# power_mux-v5.net
KiCad netlist of a schematic drawn in EAGLE
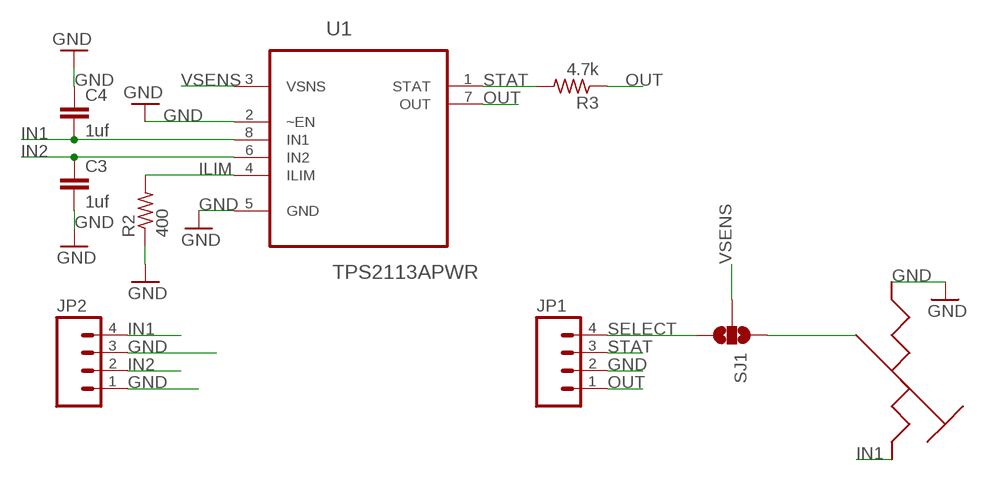
[diagram p0: schematic, sheet 1]

(export (version "E")
  (design (tool "Eeschema 10.0.6"))
  (components
    (comp (ref "C3")
      (value "1uf")
      (footprint "eagle-import:0402-CAP")
      (libsource (lib "eagle-import") (part "CAP0402-CAP"))
    )
    (comp (ref "C4")
      (value "1uf")
      (footprint "eagle-import:0402-CAP")
      (libsource (lib "eagle-import") (part "CAP0402-CAP"))
    )
    (comp (ref "JP1")
      (value "M04PTH")
      (footprint "eagle-import:1X04")
      (libsource (lib "eagle-import") (part "M04PTH"))
    )
    (comp (ref "JP2")
      (value "M04PTH")
      (footprint "eagle-import:1X04")
      (libsource (lib "eagle-import") (part "M04PTH"))
    )
    (comp (ref "R2")
      (value "400")
      (footprint "eagle-import:R0402")
      (libsource (lib "eagle-import") (part "R-US_R0402"))
    )
    (comp (ref "R3")
      (value "4.7k")
      (footprint "eagle-import:R0402")
      (libsource (lib "eagle-import") (part "R-US_R0402"))
    )
    (comp (ref "SJ1")
      (value "SOLDERJUMPER_2WAYPASTE1&2")
      (footprint "eagle-import:SJ_3_PASTE1&2")
      (libsource (lib "eagle-import") (part "SOLDERJUMPER_2WAYPASTE1&2"))
    )
    (comp (ref "U$2")
      (value "TRIMPOT-10K")
      (footprint "eagle-import:TRIMPOT-10K")
      (libsource (lib "eagle-import") (part "TRIMPOT-10K"))
    )
    (comp (ref "U1")
      (value "TPS2113APWR")
      (footprint "eagle-import:SOP65P640X120-8N")
      (libsource (lib "eagle-import") (part "TPS2113APWR"))
    )
  )
  (nets
    (net (code "1") (name "/ILIM") (class "Default")
      (node (ref "R2") (pin "2") (pinfunction "2_2") (pintype "passive"))
      (node (ref "U1") (pin "4") (pinfunction "ILIM_4") (pintype "input"))
    )
    (net (code "2") (name "/IN1") (class "Default")
      (node (ref "C4") (pin "2") (pinfunction "2_2") (pintype "passive"))
      (node (ref "JP2") (pin "4") (pinfunction "4_4") (pintype "passive"))
      (node (ref "U$2") (pin "2") (pinfunction "OUT_2") (pintype "bidirectional"))
      (node (ref "U1") (pin "8") (pinfunction "IN1_8") (pintype "input"))
    )
    (net (code "3") (name "/IN2") (class "Default")
      (node (ref "C3") (pin "1") (pinfunction "1_1") (pintype "passive"))
      (node (ref "JP2") (pin "2") (pinfunction "2_2") (pintype "passive"))
      (node (ref "U1") (pin "6") (pinfunction "IN2_6") (pintype "input"))
    )
    (net (code "4") (name "/OUT") (class "Default")
      (node (ref "JP1") (pin "1") (pinfunction "1_1") (pintype "passive"))
      (node (ref "R3") (pin "1") (pinfunction "1_1") (pintype "passive"))
      (node (ref "U1") (pin "7") (pinfunction "OUT_7") (pintype "output"))
    )
    (net (code "5") (name "/SELECT") (class "Default")
      (node (ref "JP1") (pin "4") (pinfunction "4_4") (pintype "passive"))
      (node (ref "SJ1") (pin "3") (pinfunction "3_3") (pintype "passive"))
    )
    (net (code "6") (name "/STAT") (class "Default")
      (node (ref "JP1") (pin "3") (pinfunction "3_3") (pintype "passive"))
      (node (ref "R3") (pin "2") (pinfunction "2_2") (pintype "passive"))
      (node (ref "U1") (pin "1") (pinfunction "STAT_1") (pintype "output"))
    )
    (net (code "7") (name "/VSENS") (class "Default")
      (node (ref "SJ1") (pin "2") (pinfunction "2_2") (pintype "passive"))
      (node (ref "U1") (pin "3") (pinfunction "VSNS_3") (pintype "power_in"))
    )
    (net (code "8") (name "GND") (class "Default")
      (node (ref "C3") (pin "2") (pinfunction "2_2") (pintype "passive"))
      (node (ref "C4") (pin "1") (pinfunction "1_1") (pintype "passive"))
      (node (ref "JP1") (pin "2") (pinfunction "2_2") (pintype "passive"))
      (node (ref "JP2") (pin "1") (pinfunction "1_1") (pintype "passive"))
      (node (ref "JP2") (pin "3") (pinfunction "3_3") (pintype "passive"))
      (node (ref "R2") (pin "1") (pinfunction "1_1") (pintype "passive"))
      (node (ref "U$2") (pin "1") (pinfunction "IN_1") (pintype "bidirectional"))
      (node (ref "U1") (pin "2") (pinfunction "~{EN}_2") (pintype "input"))
      (node (ref "U1") (pin "5") (pinfunction "GND_5") (pintype "passive"))
    )
    (net (code "9") (name "Net-(U$2-W)") (class "Default")
      (node (ref "SJ1") (pin "1") (pinfunction "1_1") (pintype "passive"))
      (node (ref "U$2") (pin "3") (pinfunction "W_3") (pintype "bidirectional"))
    )
  )
)
